# VME_buffers_address.net
KiCad netlist of a schematic drawn in Altium Designer
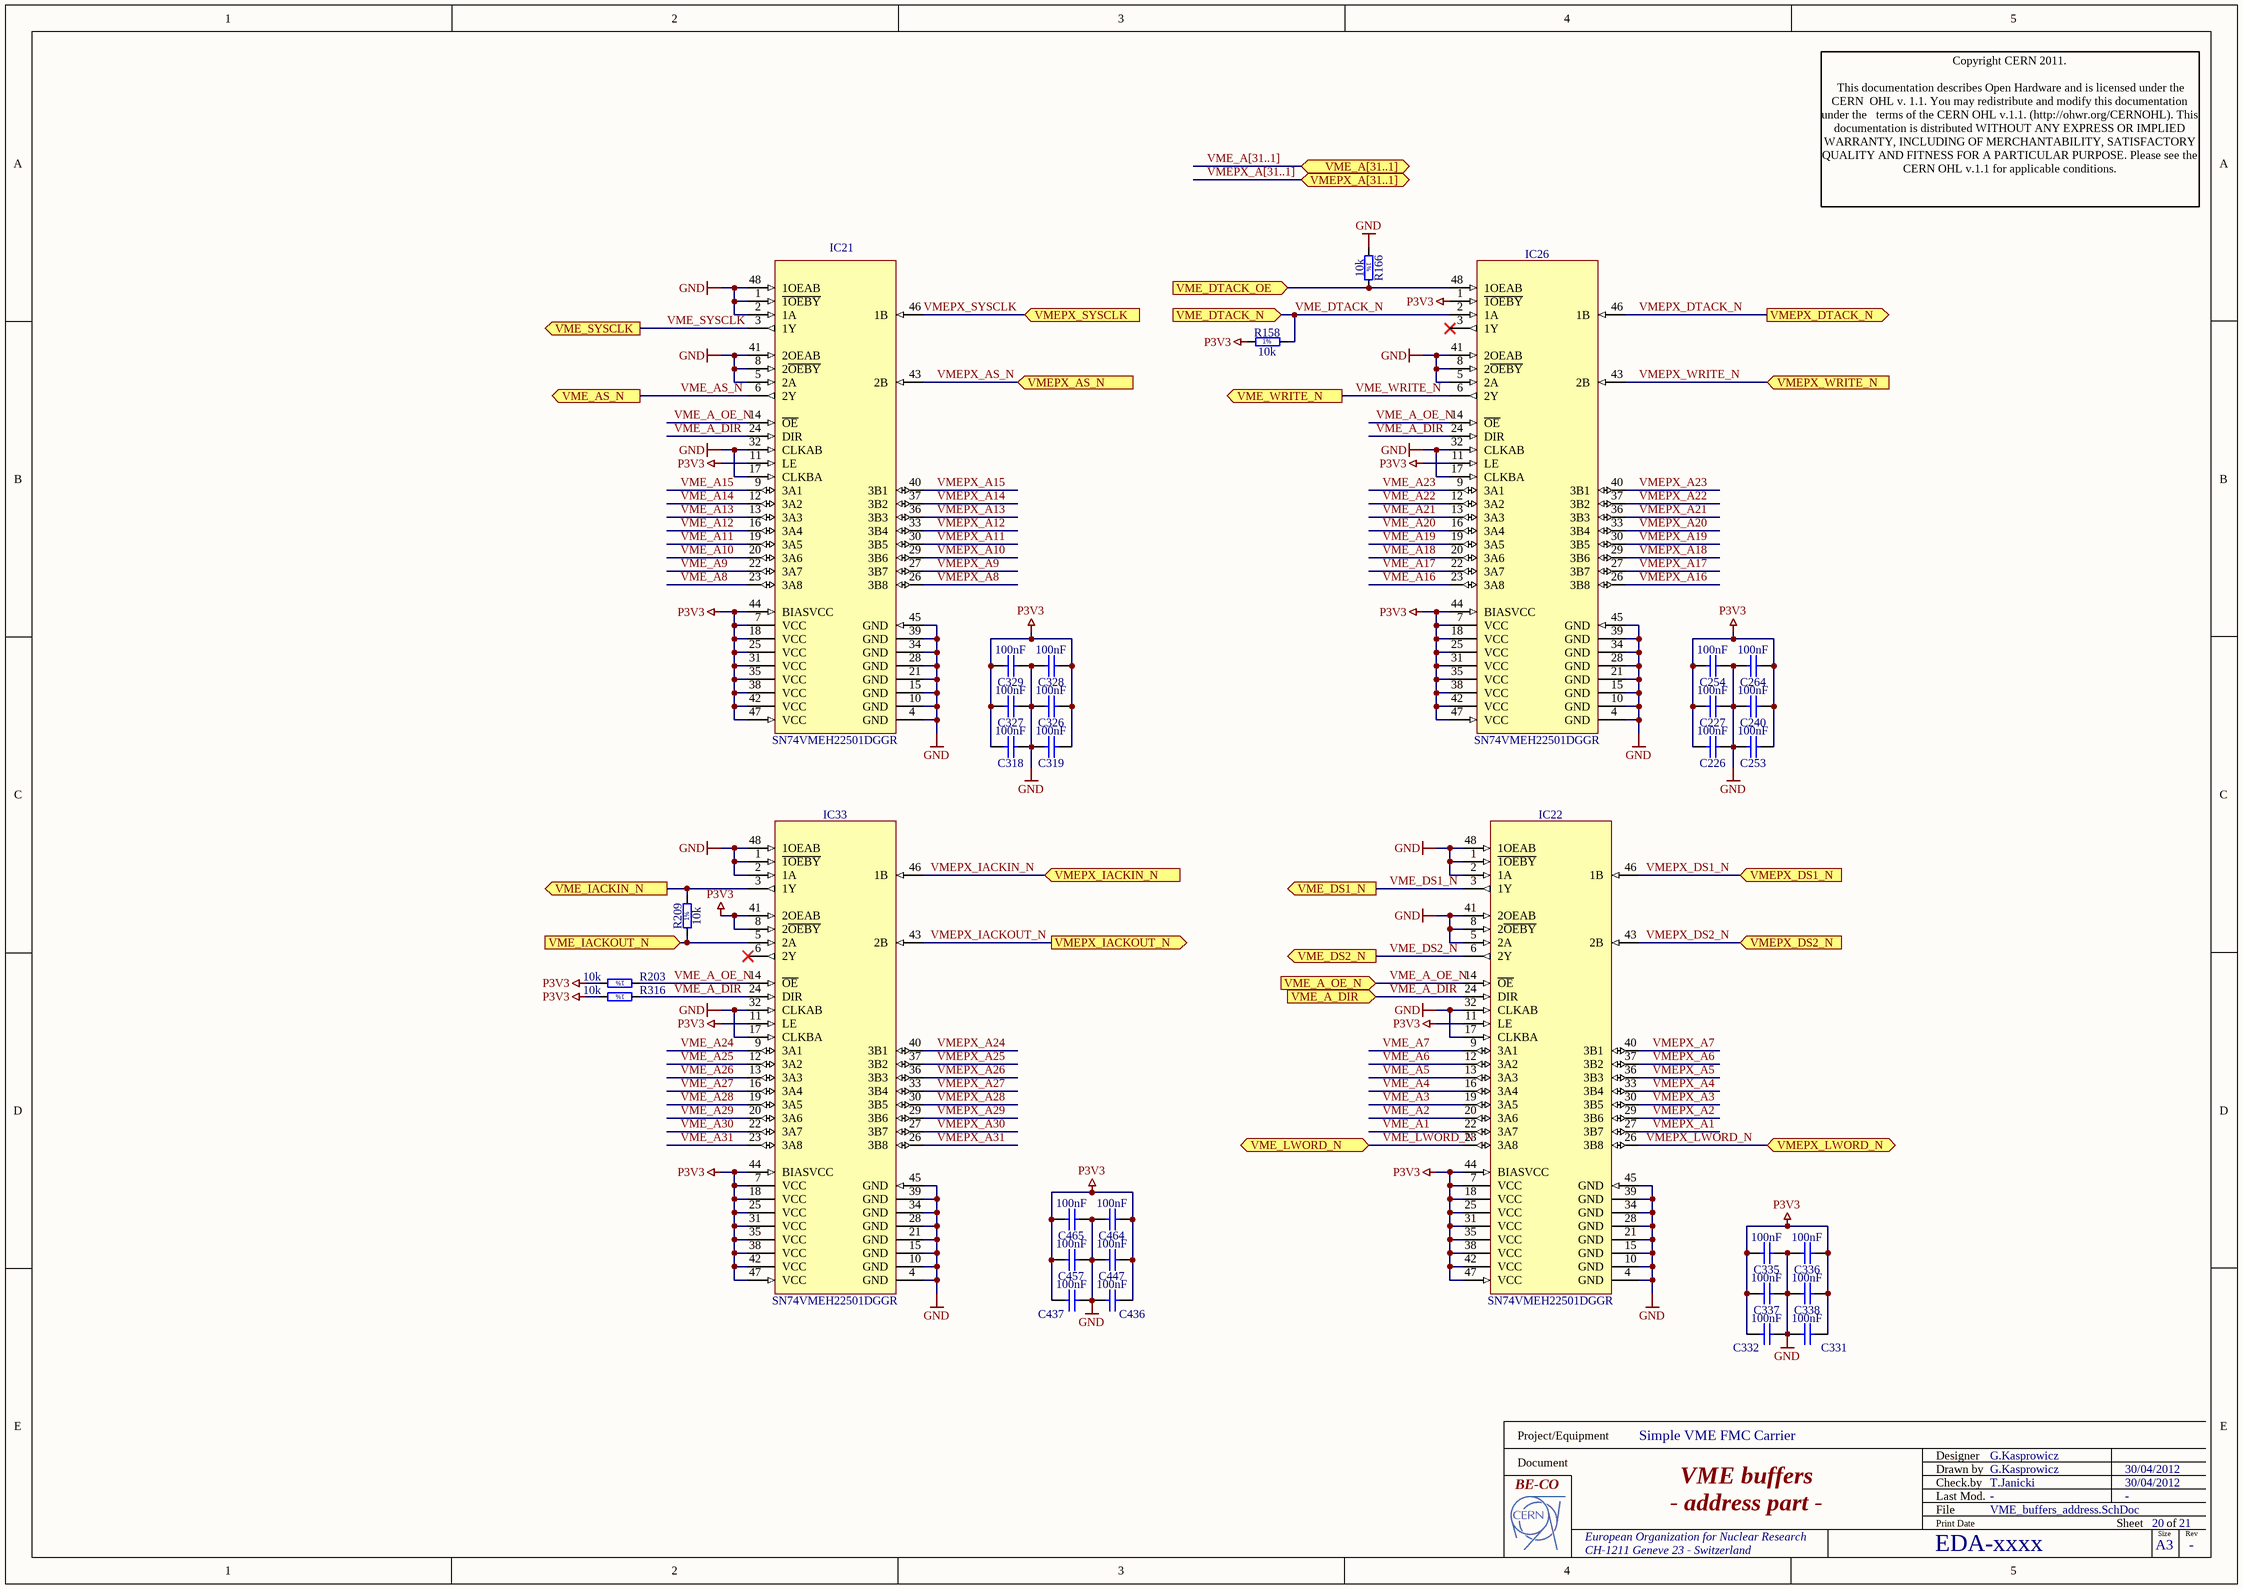
[diagram p0: VME_buffers_address.SchDoc]

(export (version "E")
  (design (tool "Eeschema 10.0.6"))
  (components
    (comp (ref "C226")
      (value "100nF")
      (footprint "CAPC1005X55N")
      (description "Non-polarised capacitor")
      (fields
        (field (name "PART NUMBER") "CC0402_100NF_16V_10%_X7R")
        (field (name "VOLTAGE") "16V")
        (field (name "AUTHOR") "CERN DEM JLC")
      )
      (libsource (lib "Capacitors") (part "Capacitor - non polarized"))
    )
    (comp (ref "C227")
      (value "100nF")
      (footprint "CAPC1005X55N")
      (description "Non-polarised capacitor")
      (fields
        (field (name "PART NUMBER") "CC0402_100NF_16V_10%_X7R")
        (field (name "VOLTAGE") "16V")
        (field (name "AUTHOR") "CERN DEM JLC")
      )
      (libsource (lib "Capacitors") (part "Capacitor - non polarized"))
    )
    (comp (ref "C240")
      (value "100nF")
      (footprint "CAPC1005X55N")
      (description "Non-polarised capacitor")
      (fields
        (field (name "PART NUMBER") "CC0402_100NF_16V_10%_X7R")
        (field (name "VOLTAGE") "16V")
        (field (name "AUTHOR") "CERN DEM JLC")
      )
      (libsource (lib "Capacitors") (part "Capacitor - non polarized"))
    )
    (comp (ref "C253")
      (value "100nF")
      (footprint "CAPC1005X55N")
      (description "Non-polarised capacitor")
      (fields
        (field (name "PART NUMBER") "CC0402_100NF_16V_10%_X7R")
        (field (name "VOLTAGE") "16V")
        (field (name "AUTHOR") "CERN DEM JLC")
      )
      (libsource (lib "Capacitors") (part "Capacitor - non polarized"))
    )
    (comp (ref "C254")
      (value "100nF")
      (footprint "CAPC1005X55N")
      (description "Non-polarised capacitor")
      (fields
        (field (name "PART NUMBER") "CC0402_100NF_16V_10%_X7R")
        (field (name "VOLTAGE") "16V")
        (field (name "AUTHOR") "CERN DEM JLC")
      )
      (libsource (lib "Capacitors") (part "Capacitor - non polarized"))
    )
    (comp (ref "C264")
      (value "100nF")
      (footprint "CAPC1005X55N")
      (description "Non-polarised capacitor")
      (fields
        (field (name "PART NUMBER") "CC0402_100NF_16V_10%_X7R")
        (field (name "VOLTAGE") "16V")
        (field (name "AUTHOR") "CERN DEM JLC")
      )
      (libsource (lib "Capacitors") (part "Capacitor - non polarized"))
    )
    (comp (ref "C318")
      (value "100nF")
      (footprint "CAPC1005X55N")
      (description "Non-polarised capacitor")
      (fields
        (field (name "PART NUMBER") "CC0402_100NF_16V_10%_X7R")
        (field (name "VOLTAGE") "16V")
        (field (name "AUTHOR") "CERN DEM JLC")
      )
      (libsource (lib "Capacitors") (part "Capacitor - non polarized"))
    )
    (comp (ref "C319")
      (value "100nF")
      (footprint "CAPC1005X55N")
      (description "Non-polarised capacitor")
      (fields
        (field (name "PART NUMBER") "CC0402_100NF_16V_10%_X7R")
        (field (name "VOLTAGE") "16V")
        (field (name "AUTHOR") "CERN DEM JLC")
      )
      (libsource (lib "Capacitors") (part "Capacitor - non polarized"))
    )
    (comp (ref "C326")
      (value "100nF")
      (footprint "CAPC1005X55N")
      (description "Non-polarised capacitor")
      (fields
        (field (name "PART NUMBER") "CC0402_100NF_16V_10%_X7R")
        (field (name "VOLTAGE") "16V")
        (field (name "AUTHOR") "CERN DEM JLC")
      )
      (libsource (lib "Capacitors") (part "Capacitor - non polarized"))
    )
    (comp (ref "C327")
      (value "100nF")
      (footprint "CAPC1005X55N")
      (description "Non-polarised capacitor")
      (fields
        (field (name "PART NUMBER") "CC0402_100NF_16V_10%_X7R")
        (field (name "VOLTAGE") "16V")
        (field (name "AUTHOR") "CERN DEM JLC")
      )
      (libsource (lib "Capacitors") (part "Capacitor - non polarized"))
    )
    (comp (ref "C328")
      (value "100nF")
      (footprint "CAPC1005X55N")
      (description "Non-polarised capacitor")
      (fields
        (field (name "PART NUMBER") "CC0402_100NF_16V_10%_X7R")
        (field (name "VOLTAGE") "16V")
        (field (name "AUTHOR") "CERN DEM JLC")
      )
      (libsource (lib "Capacitors") (part "Capacitor - non polarized"))
    )
    (comp (ref "C329")
      (value "100nF")
      (footprint "CAPC1005X55N")
      (description "Non-polarised capacitor")
      (fields
        (field (name "PART NUMBER") "CC0402_100NF_16V_10%_X7R")
        (field (name "VOLTAGE") "16V")
        (field (name "AUTHOR") "CERN DEM JLC")
      )
      (libsource (lib "Capacitors") (part "Capacitor - non polarized"))
    )
    (comp (ref "C331")
      (value "100nF")
      (footprint "CAPC1005X55N")
      (description "Non-polarised capacitor")
      (fields
        (field (name "PART NUMBER") "CC0402_100NF_16V_10%_X7R")
        (field (name "VOLTAGE") "16V")
        (field (name "AUTHOR") "CERN DEM JLC")
      )
      (libsource (lib "Capacitors") (part "Capacitor - non polarized"))
    )
    (comp (ref "C332")
      (value "100nF")
      (footprint "CAPC1005X55N")
      (description "Non-polarised capacitor")
      (fields
        (field (name "PART NUMBER") "CC0402_100NF_16V_10%_X7R")
        (field (name "VOLTAGE") "16V")
        (field (name "AUTHOR") "CERN DEM JLC")
      )
      (libsource (lib "Capacitors") (part "Capacitor - non polarized"))
    )
    (comp (ref "C335")
      (value "100nF")
      (footprint "CAPC1005X55N")
      (description "Non-polarised capacitor")
      (fields
        (field (name "PART NUMBER") "CC0402_100NF_16V_10%_X7R")
        (field (name "VOLTAGE") "16V")
        (field (name "AUTHOR") "CERN DEM JLC")
      )
      (libsource (lib "Capacitors") (part "Capacitor - non polarized"))
    )
    (comp (ref "C336")
      (value "100nF")
      (footprint "CAPC1005X55N")
      (description "Non-polarised capacitor")
      (fields
        (field (name "PART NUMBER") "CC0402_100NF_16V_10%_X7R")
        (field (name "VOLTAGE") "16V")
        (field (name "AUTHOR") "CERN DEM JLC")
      )
      (libsource (lib "Capacitors") (part "Capacitor - non polarized"))
    )
    (comp (ref "C337")
      (value "100nF")
      (footprint "CAPC1005X55N")
      (description "Non-polarised capacitor")
      (fields
        (field (name "PART NUMBER") "CC0402_100NF_16V_10%_X7R")
        (field (name "VOLTAGE") "16V")
        (field (name "AUTHOR") "CERN DEM JLC")
      )
      (libsource (lib "Capacitors") (part "Capacitor - non polarized"))
    )
    (comp (ref "C338")
      (value "100nF")
      (footprint "CAPC1005X55N")
      (description "Non-polarised capacitor")
      (fields
        (field (name "PART NUMBER") "CC0402_100NF_16V_10%_X7R")
        (field (name "VOLTAGE") "16V")
        (field (name "AUTHOR") "CERN DEM JLC")
      )
      (libsource (lib "Capacitors") (part "Capacitor - non polarized"))
    )
    (comp (ref "C436")
      (value "100nF")
      (footprint "CAPC1005X55N")
      (description "Non-polarised capacitor")
      (fields
        (field (name "PART NUMBER") "CC0402_100NF_16V_10%_X7R")
        (field (name "VOLTAGE") "16V")
        (field (name "AUTHOR") "CERN DEM JLC")
      )
      (libsource (lib "Capacitors") (part "Capacitor - non polarized"))
    )
    (comp (ref "C437")
      (value "100nF")
      (footprint "CAPC1005X55N")
      (description "Non-polarised capacitor")
      (fields
        (field (name "PART NUMBER") "CC0402_100NF_16V_10%_X7R")
        (field (name "VOLTAGE") "16V")
        (field (name "AUTHOR") "CERN DEM JLC")
      )
      (libsource (lib "Capacitors") (part "Capacitor - non polarized"))
    )
    (comp (ref "C447")
      (value "100nF")
      (footprint "CAPC1005X55N")
      (description "Non-polarised capacitor")
      (fields
        (field (name "PART NUMBER") "CC0402_100NF_16V_10%_X7R")
        (field (name "VOLTAGE") "16V")
        (field (name "AUTHOR") "CERN DEM JLC")
      )
      (libsource (lib "Capacitors") (part "Capacitor - non polarized"))
    )
    (comp (ref "C457")
      (value "100nF")
      (footprint "CAPC1005X55N")
      (description "Non-polarised capacitor")
      (fields
        (field (name "PART NUMBER") "CC0402_100NF_16V_10%_X7R")
        (field (name "VOLTAGE") "16V")
        (field (name "AUTHOR") "CERN DEM JLC")
      )
      (libsource (lib "Capacitors") (part "Capacitor - non polarized"))
    )
    (comp (ref "C464")
      (value "100nF")
      (footprint "CAPC1005X55N")
      (description "Non-polarised capacitor")
      (fields
        (field (name "PART NUMBER") "CC0402_100NF_16V_10%_X7R")
        (field (name "VOLTAGE") "16V")
        (field (name "AUTHOR") "CERN DEM JLC")
      )
      (libsource (lib "Capacitors") (part "Capacitor - non polarized"))
    )
    (comp (ref "C465")
      (value "100nF")
      (footprint "CAPC1005X55N")
      (description "Non-polarised capacitor")
      (fields
        (field (name "PART NUMBER") "CC0402_100NF_16V_10%_X7R")
        (field (name "VOLTAGE") "16V")
        (field (name "AUTHOR") "CERN DEM JLC")
      )
      (libsource (lib "Capacitors") (part "Capacitor - non polarized"))
    )
    (comp (ref "IC21")
      (value "SN74VMEH22501DGGR")
      (footprint "SOP50P810X120-48N")
      (description "8-Bit Universal Bus Transceiver and Two 1-Bit Bus Transceivers with 3-State Outputs")
      (fields (field (name "MANUFACTURER") "TEXAS INSTRUMENTS") (field (name "AUTHOR") "CERN DEM JLC"))
      (libsource (lib "ICs And Semiconductors") (part "74VMEH22501"))
    )
    (comp (ref "IC22")
      (value "SN74VMEH22501DGGR")
      (footprint "SOP50P810X120-48N")
      (description "8-Bit Universal Bus Transceiver and Two 1-Bit Bus Transceivers with 3-State Outputs")
      (fields (field (name "MANUFACTURER") "TEXAS INSTRUMENTS") (field (name "AUTHOR") "CERN DEM JLC"))
      (libsource (lib "ICs And Semiconductors") (part "74VMEH22501"))
    )
    (comp (ref "IC26")
      (value "SN74VMEH22501DGGR")
      (footprint "SOP50P810X120-48N")
      (description "8-Bit Universal Bus Transceiver and Two 1-Bit Bus Transceivers with 3-State Outputs")
      (fields (field (name "MANUFACTURER") "TEXAS INSTRUMENTS") (field (name "AUTHOR") "CERN DEM JLC"))
      (libsource (lib "ICs And Semiconductors") (part "74VMEH22501"))
    )
    (comp (ref "IC33")
      (value "SN74VMEH22501DGGR")
      (footprint "SOP50P810X120-48N")
      (description "8-Bit Universal Bus Transceiver and Two 1-Bit Bus Transceivers with 3-State Outputs")
      (fields (field (name "MANUFACTURER") "TEXAS INSTRUMENTS") (field (name "AUTHOR") "CERN DEM JLC"))
      (libsource (lib "ICs And Semiconductors") (part "74VMEH22501"))
    )
    (comp (ref "R158")
      (value "10k")
      (footprint "RESC1608X55N")
      (description "Resistor - 1%")
      (fields
        (field (name "PART NUMBER") "R0603_10K_1%_0.1W_100PPM")
        (field (name "POWER") "0.1W")
        (field (name "AUTHOR") "CERN DEM JLC")
      )
      (libsource (lib "Resistors") (part "Resistor - 1%"))
    )
    (comp (ref "R166")
      (value "10k")
      (footprint "RESC1608X55N")
      (description "Resistor - 1%")
      (fields
        (field (name "PART NUMBER") "R0603_10K_1%_0.1W_100PPM")
        (field (name "POWER") "0.1W")
        (field (name "AUTHOR") "CERN DEM JLC")
      )
      (libsource (lib "Resistors") (part "Resistor - 1%"))
    )
    (comp (ref "R203")
      (value "10k")
      (footprint "RESC1608X55N")
      (description "Resistor - 1%")
      (fields
        (field (name "PART NUMBER") "R0603_10K_1%_0.1W_100PPM")
        (field (name "POWER") "0.1W")
        (field (name "AUTHOR") "CERN DEM JLC")
      )
      (libsource (lib "Resistors") (part "Resistor - 1%"))
    )
    (comp (ref "R209")
      (value "10k")
      (footprint "RESC1608X55N")
      (description "Resistor - 1%")
      (fields
        (field (name "PART NUMBER") "R0603_10K_1%_0.1W_100PPM")
        (field (name "POWER") "0.1W")
        (field (name "AUTHOR") "CERN DEM JLC")
      )
      (libsource (lib "Resistors") (part "Resistor - 1%"))
    )
    (comp (ref "R316")
      (value "10k")
      (footprint "RESC1608X55N")
      (description "Resistor - 1%")
      (fields
        (field (name "PART NUMBER") "R0603_10K_1%_0.1W_100PPM")
        (field (name "POWER") "0.1W")
        (field (name "AUTHOR") "CERN DEM JLC")
      )
      (libsource (lib "Resistors") (part "Resistor - 1%"))
    )
  )
  (nets
    (net (code "1") (name "/VMEPX_A1") (class "Default")
      (node (ref "IC22") (pin "27") (pinfunction "3B7_27") (pintype "bidirectional"))
    )
    (net (code "2") (name "/VMEPX_A2") (class "Default")
      (node (ref "IC22") (pin "29") (pinfunction "3B6_29") (pintype "bidirectional"))
    )
    (net (code "3") (name "/VMEPX_A3") (class "Default")
      (node (ref "IC22") (pin "30") (pinfunction "3B5_30") (pintype "bidirectional"))
    )
    (net (code "4") (name "/VMEPX_A4") (class "Default")
      (node (ref "IC22") (pin "33") (pinfunction "3B4_33") (pintype "bidirectional"))
    )
    (net (code "5") (name "/VMEPX_A5") (class "Default")
      (node (ref "IC22") (pin "36") (pinfunction "3B3_36") (pintype "bidirectional"))
    )
    (net (code "6") (name "/VMEPX_A6") (class "Default")
      (node (ref "IC22") (pin "37") (pinfunction "3B2_37") (pintype "bidirectional"))
    )
    (net (code "7") (name "/VMEPX_A7") (class "Default")
      (node (ref "IC22") (pin "40") (pinfunction "3B1_40") (pintype "bidirectional"))
    )
    (net (code "8") (name "/VMEPX_A8") (class "Default")
      (node (ref "IC21") (pin "26") (pinfunction "3B8_26") (pintype "bidirectional"))
    )
    (net (code "9") (name "/VMEPX_A9") (class "Default")
      (node (ref "IC21") (pin "27") (pinfunction "3B7_27") (pintype "bidirectional"))
    )
    (net (code "10") (name "/VMEPX_A10") (class "Default")
      (node (ref "IC21") (pin "29") (pinfunction "3B6_29") (pintype "bidirectional"))
    )
    (net (code "11") (name "/VMEPX_A11") (class "Default")
      (node (ref "IC21") (pin "30") (pinfunction "3B5_30") (pintype "bidirectional"))
    )
    (net (code "12") (name "/VMEPX_A12") (class "Default")
      (node (ref "IC21") (pin "33") (pinfunction "3B4_33") (pintype "bidirectional"))
    )
    (net (code "13") (name "/VMEPX_A13") (class "Default")
      (node (ref "IC21") (pin "36") (pinfunction "3B3_36") (pintype "bidirectional"))
    )
    (net (code "14") (name "/VMEPX_A14") (class "Default")
      (node (ref "IC21") (pin "37") (pinfunction "3B2_37") (pintype "bidirectional"))
    )
    (net (code "15") (name "/VMEPX_A15") (class "Default")
      (node (ref "IC21") (pin "40") (pinfunction "3B1_40") (pintype "bidirectional"))
    )
    (net (code "16") (name "/VMEPX_A16") (class "Default")
      (node (ref "IC26") (pin "26") (pinfunction "3B8_26") (pintype "bidirectional"))
    )
    (net (code "17") (name "/VMEPX_A17") (class "Default")
      (node (ref "IC26") (pin "27") (pinfunction "3B7_27") (pintype "bidirectional"))
    )
    (net (code "18") (name "/VMEPX_A18") (class "Default")
      (node (ref "IC26") (pin "29") (pinfunction "3B6_29") (pintype "bidirectional"))
    )
    (net (code "19") (name "/VMEPX_A19") (class "Default")
      (node (ref "IC26") (pin "30") (pinfunction "3B5_30") (pintype "bidirectional"))
    )
    (net (code "20") (name "/VMEPX_A20") (class "Default")
      (node (ref "IC26") (pin "33") (pinfunction "3B4_33") (pintype "bidirectional"))
    )
    (net (code "21") (name "/VMEPX_A21") (class "Default")
      (node (ref "IC26") (pin "36") (pinfunction "3B3_36") (pintype "bidirectional"))
    )
    (net (code "22") (name "/VMEPX_A22") (class "Default")
      (node (ref "IC26") (pin "37") (pinfunction "3B2_37") (pintype "bidirectional"))
    )
    (net (code "23") (name "/VMEPX_A23") (class "Default")
      (node (ref "IC26") (pin "40") (pinfunction "3B1_40") (pintype "bidirectional"))
    )
    (net (code "24") (name "/VMEPX_A24") (class "Default")
      (node (ref "IC33") (pin "40") (pinfunction "3B1_40") (pintype "bidirectional"))
    )
    (net (code "25") (name "/VMEPX_A25") (class "Default")
      (node (ref "IC33") (pin "37") (pinfunction "3B2_37") (pintype "bidirectional"))
    )
    (net (code "26") (name "/VMEPX_A26") (class "Default")
      (node (ref "IC33") (pin "36") (pinfunction "3B3_36") (pintype "bidirectional"))
    )
    (net (code "27") (name "/VMEPX_A27") (class "Default")
      (node (ref "IC33") (pin "33") (pinfunction "3B4_33") (pintype "bidirectional"))
    )
    (net (code "28") (name "/VMEPX_A28") (class "Default")
      (node (ref "IC33") (pin "30") (pinfunction "3B5_30") (pintype "bidirectional"))
    )
    (net (code "29") (name "/VMEPX_A29") (class "Default")
      (node (ref "IC33") (pin "29") (pinfunction "3B6_29") (pintype "bidirectional"))
    )
    (net (code "30") (name "/VMEPX_A30") (class "Default")
      (node (ref "IC33") (pin "27") (pinfunction "3B7_27") (pintype "bidirectional"))
    )
    (net (code "31") (name "/VMEPX_A31") (class "Default")
      (node (ref "IC33") (pin "26") (pinfunction "3B8_26") (pintype "bidirectional"))
    )
    (net (code "32") (name "/VMEPX_AS_N") (class "Default")
      (node (ref "IC21") (pin "43") (pinfunction "2B_43") (pintype "input"))
    )
    (net (code "34") (name "/VMEPX_DS1_N") (class "Default")
      (node (ref "IC22") (pin "46") (pinfunction "1B_46") (pintype "input"))
    )
    (net (code "35") (name "/VMEPX_DS2_N") (class "Default")
      (node (ref "IC22") (pin "43") (pinfunction "2B_43") (pintype "input"))
    )
    (net (code "36") (name "/VMEPX_DTACK_N") (class "Default")
      (node (ref "IC26") (pin "46") (pinfunction "1B_46") (pintype "input"))
    )
    (net (code "37") (name "/VMEPX_IACKIN_N") (class "Default")
      (node (ref "IC33") (pin "46") (pinfunction "1B_46") (pintype "input"))
    )
    (net (code "38") (name "/VMEPX_IACKOUT_N") (class "Default")
      (node (ref "IC33") (pin "43") (pinfunction "2B_43") (pintype "input"))
    )
    (net (code "39") (name "/VMEPX_LWORD_N") (class "Default")
      (node (ref "IC22") (pin "26") (pinfunction "3B8_26") (pintype "bidirectional"))
    )
    (net (code "40") (name "/VMEPX_SYSCLK") (class "Default")
      (node (ref "IC21") (pin "46") (pinfunction "1B_46") (pintype "input"))
    )
    (net (code "41") (name "/VMEPX_WRITE_N") (class "Default")
      (node (ref "IC26") (pin "43") (pinfunction "2B_43") (pintype "input"))
    )
    (net (code "42") (name "/VME_A1") (class "Default")
      (node (ref "IC22") (pin "22") (pinfunction "3A7_22") (pintype "bidirectional"))
    )
    (net (code "43") (name "/VME_A2") (class "Default")
      (node (ref "IC22") (pin "20") (pinfunction "3A6_20") (pintype "bidirectional"))
    )
    (net (code "44") (name "/VME_A3") (class "Default")
      (node (ref "IC22") (pin "19") (pinfunction "3A5_19") (pintype "bidirectional"))
    )
    (net (code "45") (name "/VME_A4") (class "Default")
      (node (ref "IC22") (pin "16") (pinfunction "3A4_16") (pintype "bidirectional"))
    )
    (net (code "46") (name "/VME_A5") (class "Default")
      (node (ref "IC22") (pin "13") (pinfunction "3A3_13") (pintype "bidirectional"))
    )
    (net (code "47") (name "/VME_A6") (class "Default")
      (node (ref "IC22") (pin "12") (pinfunction "3A2_12") (pintype "bidirectional"))
    )
    (net (code "48") (name "/VME_A7") (class "Default")
      (node (ref "IC22") (pin "9") (pinfunction "3A1_9") (pintype "bidirectional"))
    )
    (net (code "49") (name "/VME_A8") (class "Default")
      (node (ref "IC21") (pin "23") (pinfunction "3A8_23") (pintype "bidirectional"))
    )
    (net (code "50") (name "/VME_A9") (class "Default")
      (node (ref "IC21") (pin "22") (pinfunction "3A7_22") (pintype "bidirectional"))
    )
    (net (code "51") (name "/VME_A10") (class "Default")
      (node (ref "IC21") (pin "20") (pinfunction "3A6_20") (pintype "bidirectional"))
    )
    (net (code "52") (name "/VME_A11") (class "Default")
      (node (ref "IC21") (pin "19") (pinfunction "3A5_19") (pintype "bidirectional"))
    )
    (net (code "53") (name "/VME_A12") (class "Default")
      (node (ref "IC21") (pin "16") (pinfunction "3A4_16") (pintype "bidirectional"))
    )
    (net (code "54") (name "/VME_A13") (class "Default")
      (node (ref "IC21") (pin "13") (pinfunction "3A3_13") (pintype "bidirectional"))
    )
    (net (code "55") (name "/VME_A14") (class "Default")
      (node (ref "IC21") (pin "12") (pinfunction "3A2_12") (pintype "bidirectional"))
    )
    (net (code "56") (name "/VME_A15") (class "Default")
      (node (ref "IC21") (pin "9") (pinfunction "3A1_9") (pintype "bidirectional"))
    )
    (net (code "57") (name "/VME_A16") (class "Default")
      (node (ref "IC26") (pin "23") (pinfunction "3A8_23") (pintype "bidirectional"))
    )
    (net (code "58") (name "/VME_A17") (class "Default")
      (node (ref "IC26") (pin "22") (pinfunction "3A7_22") (pintype "bidirectional"))
    )
    (net (code "59") (name "/VME_A18") (class "Default")
      (node (ref "IC26") (pin "20") (pinfunction "3A6_20") (pintype "bidirectional"))
    )
    (net (code "60") (name "/VME_A19") (class "Default")
      (node (ref "IC26") (pin "19") (pinfunction "3A5_19") (pintype "bidirectional"))
    )
    (net (code "61") (name "/VME_A20") (class "Default")
      (node (ref "IC26") (pin "16") (pinfunction "3A4_16") (pintype "bidirectional"))
    )
    (net (code "62") (name "/VME_A21") (class "Default")
      (node (ref "IC26") (pin "13") (pinfunction "3A3_13") (pintype "bidirectional"))
    )
    (net (code "63") (name "/VME_A22") (class "Default")
      (node (ref "IC26") (pin "12") (pinfunction "3A2_12") (pintype "bidirectional"))
    )
    (net (code "64") (name "/VME_A23") (class "Default")
      (node (ref "IC26") (pin "9") (pinfunction "3A1_9") (pintype "bidirectional"))
    )
    (net (code "65") (name "/VME_A24") (class "Default")
      (node (ref "IC33") (pin "9") (pinfunction "3A1_9") (pintype "bidirectional"))
    )
    (net (code "66") (name "/VME_A25") (class "Default")
      (node (ref "IC33") (pin "12") (pinfunction "3A2_12") (pintype "bidirectional"))
    )
    (net (code "67") (name "/VME_A26") (class "Default")
      (node (ref "IC33") (pin "13") (pinfunction "3A3_13") (pintype "bidirectional"))
    )
    (net (code "68") (name "/VME_A27") (class "Default")
      (node (ref "IC33") (pin "16") (pinfunction "3A4_16") (pintype "bidirectional"))
    )
    (net (code "69") (name "/VME_A28") (class "Default")
      (node (ref "IC33") (pin "19") (pinfunction "3A5_19") (pintype "bidirectional"))
    )
    (net (code "70") (name "/VME_A29") (class "Default")
      (node (ref "IC33") (pin "20") (pinfunction "3A6_20") (pintype "bidirectional"))
    )
    (net (code "71") (name "/VME_A30") (class "Default")
      (node (ref "IC33") (pin "22") (pinfunction "3A7_22") (pintype "bidirectional"))
    )
    (net (code "72") (name "/VME_A31") (class "Default")
      (node (ref "IC33") (pin "23") (pinfunction "3A8_23") (pintype "bidirectional"))
    )
    (net (code "73") (name "/VME_AS_N") (class "Default")
      (node (ref "IC21") (pin "6") (pinfunction "2Y_6") (pintype "output"))
    )
    (net (code "75") (name "/VME_A_DIR") (class "Default")
      (node (ref "IC21") (pin "24") (pinfunction "DIR_24") (pintype "input"))
      (node (ref "IC22") (pin "24") (pinfunction "DIR_24") (pintype "input"))
      (node (ref "IC26") (pin "24") (pinfunction "DIR_24") (pintype "input"))
      (node (ref "IC33") (pin "24") (pinfunction "DIR_24") (pintype "input"))
      (node (ref "R316") (pin "1") (pinfunction "1_1") (pintype "passive"))
    )
    (net (code "76") (name "/VME_A_OE_N") (class "Default")
      (node (ref "IC21") (pin "14") (pinfunction "~{OE}_14") (pintype "input"))
      (node (ref "IC22") (pin "14") (pinfunction "~{OE}_14") (pintype "input"))
      (node (ref "IC26") (pin "14") (pinfunction "~{OE}_14") (pintype "input"))
      (node (ref "IC33") (pin "14") (pinfunction "~{OE}_14") (pintype "input"))
      (node (ref "R203") (pin "1") (pinfunction "1_1") (pintype "passive"))
    )
    (net (code "77") (name "/VME_DS1_N") (class "Default")
      (node (ref "IC22") (pin "3") (pinfunction "1Y_3") (pintype "output"))
    )
    (net (code "78") (name "/VME_DS2_N") (class "Default")
      (node (ref "IC22") (pin "6") (pinfunction "2Y_6") (pintype "output"))
    )
    (net (code "79") (name "/VME_DTACK_N") (class "Default")
      (node (ref "IC26") (pin "2") (pinfunction "1A_2") (pintype "input"))
      (node (ref "R158") (pin "2") (pinfunction "2_2") (pintype "passive"))
    )
    (net (code "80") (name "/VME_DTACK_OE") (class "Default")
      (node (ref "IC26") (pin "48") (pinfunction "1OEAB_48") (pintype "input"))
      (node (ref "R166") (pin "2") (pinfunction "2_2") (pintype "passive"))
    )
    (net (code "81") (name "/VME_IACKIN_N") (class "Default")
      (node (ref "IC33") (pin "3") (pinfunction "1Y_3") (pintype "output"))
      (node (ref "R209") (pin "2") (pinfunction "2_2") (pintype "passive"))
    )
    (net (code "82") (name "/VME_IACKOUT_N") (class "Default")
      (node (ref "IC33") (pin "5") (pinfunction "2A_5") (pintype "input"))
      (node (ref "R209") (pin "1") (pinfunction "1_1") (pintype "passive"))
    )
    (net (code "83") (name "/VME_LWORD_N") (class "Default")
      (node (ref "IC22") (pin "23") (pinfunction "3A8_23") (pintype "bidirectional"))
    )
    (net (code "84") (name "/VME_SYSCLK") (class "Default")
      (node (ref "IC21") (pin "3") (pinfunction "1Y_3") (pintype "output"))
    )
    (net (code "85") (name "/VME_WRITE_N") (class "Default")
      (node (ref "IC26") (pin "6") (pinfunction "2Y_6") (pintype "output"))
    )
    (net (code "86") (name "GND") (class "Default")
      (node (ref "C226") (pin "1") (pinfunction "1_1") (pintype "passive"))
      (node (ref "C227") (pin "1") (pinfunction "1_1") (pintype "passive"))
      (node (ref "C240") (pin "2") (pinfunction "2_2") (pintype "passive"))
      (node (ref "C253") (pin "2") (pinfunction "2_2") (pintype "passive"))
      (node (ref "C254") (pin "1") (pinfunction "1_1") (pintype "passive"))
      (node (ref "C264") (pin "2") (pinfunction "2_2") (pintype "passive"))
      (node (ref "C318") (pin "1") (pinfunction "1_1") (pintype "passive"))
      (node (ref "C319") (pin "2") (pinfunction "2_2") (pintype "passive"))
      (node (ref "C326") (pin "2") (pinfunction "2_2") (pintype "passive"))
      (node (ref "C327") (pin "1") (pinfunction "1_1") (pintype "passive"))
      (node (ref "C328") (pin "2") (pinfunction "2_2") (pintype "passive"))
      (node (ref "C329") (pin "1") (pinfunction "1_1") (pintype "passive"))
      (node (ref "C331") (pin "2") (pinfunction "2_2") (pintype "passive"))
      (node (ref "C332") (pin "1") (pinfunction "1_1") (pintype "passive"))
      (node (ref "C335") (pin "1") (pinfunction "1_1") (pintype "passive"))
      (node (ref "C336") (pin "2") (pinfunction "2_2") (pintype "passive"))
      (node (ref "C337") (pin "1") (pinfunction "1_1") (pintype "passive"))
      (node (ref "C338") (pin "2") (pinfunction "2_2") (pintype "passive"))
      (node (ref "C436") (pin "2") (pinfunction "2_2") (pintype "passive"))
      (node (ref "C437") (pin "1") (pinfunction "1_1") (pintype "passive"))
      (node (ref "C447") (pin "2") (pinfunction "2_2") (pintype "passive"))
      (node (ref "C457") (pin "1") (pinfunction "1_1") (pintype "passive"))
      (node (ref "C464") (pin "2") (pinfunction "2_2") (pintype "passive"))
      (node (ref "C465") (pin "1") (pinfunction "1_1") (pintype "passive"))
      (node (ref "IC21") (pin "1") (pinfunction "~{1OEBY}_1") (pintype "input"))
      (node (ref "IC21") (pin "10") (pinfunction "GND_10") (pintype "power_in"))
      (node (ref "IC21") (pin "15") (pinfunction "GND_15") (pintype "power_in"))
      (node (ref "IC21") (pin "17") (pinfunction "CLKBA_17") (pintype "input"))
      (node (ref "IC21") (pin "2") (pinfunction "1A_2") (pintype "input"))
      (node (ref "IC21") (pin "21") (pinfunction "GND_21") (pintype "power_in"))
      (node (ref "IC21") (pin "28") (pinfunction "GND_28") (pintype "power_in"))
      (node (ref "IC21") (pin "32") (pinfunction "CLKAB_32") (pintype "input"))
      (node (ref "IC21") (pin "34") (pinfunction "GND_34") (pintype "power_in"))
      (node (ref "IC21") (pin "39") (pinfunction "GND_39") (pintype "power_in"))
      (node (ref "IC21") (pin "4") (pinfunction "GND_4") (pintype "power_in"))
      (node (ref "IC21") (pin "41") (pinfunction "2OEAB_41") (pintype "input"))
      (node (ref "IC21") (pin "45") (pinfunction "GND_45") (pintype "input"))
      (node (ref "IC21") (pin "48") (pinfunction "1OEAB_48") (pintype "input"))
      (node (ref "IC21") (pin "5") (pinfunction "2A_5") (pintype "input"))
      (node (ref "IC21") (pin "8") (pinfunction "2~{OEBY}_8") (pintype "input"))
      (node (ref "IC22") (pin "1") (pinfunction "~{1OEBY}_1") (pintype "input"))
      (node (ref "IC22") (pin "10") (pinfunction "GND_10") (pintype "power_in"))
      (node (ref "IC22") (pin "15") (pinfunction "GND_15") (pintype "power_in"))
      (node (ref "IC22") (pin "17") (pinfunction "CLKBA_17") (pintype "input"))
      (node (ref "IC22") (pin "2") (pinfunction "1A_2") (pintype "input"))
      (node (ref "IC22") (pin "21") (pinfunction "GND_21") (pintype "power_in"))
      (node (ref "IC22") (pin "28") (pinfunction "GND_28") (pintype "power_in"))
      (node (ref "IC22") (pin "32") (pinfunction "CLKAB_32") (pintype "input"))
      (node (ref "IC22") (pin "34") (pinfunction "GND_34") (pintype "power_in"))
      (node (ref "IC22") (pin "39") (pinfunction "GND_39") (pintype "power_in"))
      (node (ref "IC22") (pin "4") (pinfunction "GND_4") (pintype "power_in"))
      (node (ref "IC22") (pin "41") (pinfunction "2OEAB_41") (pintype "input"))
      (node (ref "IC22") (pin "45") (pinfunction "GND_45") (pintype "input"))
      (node (ref "IC22") (pin "48") (pinfunction "1OEAB_48") (pintype "input"))
      (node (ref "IC22") (pin "5") (pinfunction "2A_5") (pintype "input"))
      (node (ref "IC22") (pin "8") (pinfunction "2~{OEBY}_8") (pintype "input"))
      (node (ref "IC26") (pin "10") (pinfunction "GND_10") (pintype "power_in"))
      (node (ref "IC26") (pin "15") (pinfunction "GND_15") (pintype "power_in"))
      (node (ref "IC26") (pin "17") (pinfunction "CLKBA_17") (pintype "input"))
      (node (ref "IC26") (pin "21") (pinfunction "GND_21") (pintype "power_in"))
      (node (ref "IC26") (pin "28") (pinfunction "GND_28") (pintype "power_in"))
      (node (ref "IC26") (pin "32") (pinfunction "CLKAB_32") (pintype "input"))
      (node (ref "IC26") (pin "34") (pinfunction "GND_34") (pintype "power_in"))
      (node (ref "IC26") (pin "39") (pinfunction "GND_39") (pintype "power_in"))
      (node (ref "IC26") (pin "4") (pinfunction "GND_4") (pintype "power_in"))
      (node (ref "IC26") (pin "41") (pinfunction "2OEAB_41") (pintype "input"))
      (node (ref "IC26") (pin "45") (pinfunction "GND_45") (pintype "input"))
      (node (ref "IC26") (pin "5") (pinfunction "2A_5") (pintype "input"))
      (node (ref "IC26") (pin "8") (pinfunction "2~{OEBY}_8") (pintype "input"))
      (node (ref "IC33") (pin "1") (pinfunction "~{1OEBY}_1") (pintype "input"))
      (node (ref "IC33") (pin "10") (pinfunction "GND_10") (pintype "power_in"))
      (node (ref "IC33") (pin "15") (pinfunction "GND_15") (pintype "power_in"))
      (node (ref "IC33") (pin "17") (pinfunction "CLKBA_17") (pintype "input"))
      (node (ref "IC33") (pin "2") (pinfunction "1A_2") (pintype "input"))
      (node (ref "IC33") (pin "21") (pinfunction "GND_21") (pintype "power_in"))
      (node (ref "IC33") (pin "28") (pinfunction "GND_28") (pintype "power_in"))
      (node (ref "IC33") (pin "32") (pinfunction "CLKAB_32") (pintype "input"))
      (node (ref "IC33") (pin "34") (pinfunction "GND_34") (pintype "power_in"))
      (node (ref "IC33") (pin "39") (pinfunction "GND_39") (pintype "power_in"))
      (node (ref "IC33") (pin "4") (pinfunction "GND_4") (pintype "power_in"))
      (node (ref "IC33") (pin "45") (pinfunction "GND_45") (pintype "input"))
      (node (ref "IC33") (pin "48") (pinfunction "1OEAB_48") (pintype "input"))
      (node (ref "R166") (pin "1") (pinfunction "1_1") (pintype "passive"))
    )
    (net (code "87") (name "P3V3") (class "Default")
      (node (ref "C226") (pin "2") (pinfunction "2_2") (pintype "passive"))
      (node (ref "C227") (pin "2") (pinfunction "2_2") (pintype "passive"))
      (node (ref "C240") (pin "1") (pinfunction "1_1") (pintype "passive"))
      (node (ref "C253") (pin "1") (pinfunction "1_1") (pintype "passive"))
      (node (ref "C254") (pin "2") (pinfunction "2_2") (pintype "passive"))
      (node (ref "C264") (pin "1") (pinfunction "1_1") (pintype "passive"))
      (node (ref "C318") (pin "2") (pinfunction "2_2") (pintype "passive"))
      (node (ref "C319") (pin "1") (pinfunction "1_1") (pintype "passive"))
      (node (ref "C326") (pin "1") (pinfunction "1_1") (pintype "passive"))
      (node (ref "C327") (pin "2") (pinfunction "2_2") (pintype "passive"))
      (node (ref "C328") (pin "1") (pinfunction "1_1") (pintype "passive"))
      (node (ref "C329") (pin "2") (pinfunction "2_2") (pintype "passive"))
      (node (ref "C331") (pin "1") (pinfunction "1_1") (pintype "passive"))
      (node (ref "C332") (pin "2") (pinfunction "2_2") (pintype "passive"))
      (node (ref "C335") (pin "2") (pinfunction "2_2") (pintype "passive"))
      (node (ref "C336") (pin "1") (pinfunction "1_1") (pintype "passive"))
      (node (ref "C337") (pin "2") (pinfunction "2_2") (pintype "passive"))
      (node (ref "C338") (pin "1") (pinfunction "1_1") (pintype "passive"))
      (node (ref "C436") (pin "1") (pinfunction "1_1") (pintype "passive"))
      (node (ref "C437") (pin "2") (pinfunction "2_2") (pintype "passive"))
      (node (ref "C447") (pin "1") (pinfunction "1_1") (pintype "passive"))
      (node (ref "C457") (pin "2") (pinfunction "2_2") (pintype "passive"))
      (node (ref "C464") (pin "1") (pinfunction "1_1") (pintype "passive"))
      (node (ref "C465") (pin "2") (pinfunction "2_2") (pintype "passive"))
      (node (ref "IC21") (pin "11") (pinfunction "LE_11") (pintype "input"))
      (node (ref "IC21") (pin "18") (pinfunction "VCC_18") (pintype "power_in"))
      (node (ref "IC21") (pin "25") (pinfunction "VCC_25") (pintype "power_in"))
      (node (ref "IC21") (pin "31") (pinfunction "VCC_31") (pintype "power_in"))
      (node (ref "IC21") (pin "35") (pinfunction "VCC_35") (pintype "power_in"))
      (node (ref "IC21") (pin "38") (pinfunction "VCC_38") (pintype "power_in"))
      (node (ref "IC21") (pin "42") (pinfunction "VCC_42") (pintype "power_in"))
      (node (ref "IC21") (pin "44") (pinfunction "BIASVCC_44") (pintype "input"))
      (node (ref "IC21") (pin "47") (pinfunction "VCC_47") (pintype "input"))
      (node (ref "IC21") (pin "7") (pinfunction "VCC_7") (pintype "power_in"))
      (node (ref "IC22") (pin "11") (pinfunction "LE_11") (pintype "input"))
      (node (ref "IC22") (pin "18") (pinfunction "VCC_18") (pintype "power_in"))
      (node (ref "IC22") (pin "25") (pinfunction "VCC_25") (pintype "power_in"))
      (node (ref "IC22") (pin "31") (pinfunction "VCC_31") (pintype "power_in"))
      (node (ref "IC22") (pin "35") (pinfunction "VCC_35") (pintype "power_in"))
      (node (ref "IC22") (pin "38") (pinfunction "VCC_38") (pintype "power_in"))
      (node (ref "IC22") (pin "42") (pinfunction "VCC_42") (pintype "power_in"))
      (node (ref "IC22") (pin "44") (pinfunction "BIASVCC_44") (pintype "input"))
      (node (ref "IC22") (pin "47") (pinfunction "VCC_47") (pintype "input"))
      (node (ref "IC22") (pin "7") (pinfunction "VCC_7") (pintype "power_in"))
      (node (ref "IC26") (pin "1") (pinfunction "~{1OEBY}_1") (pintype "input"))
      (node (ref "IC26") (pin "11") (pinfunction "LE_11") (pintype "input"))
      (node (ref "IC26") (pin "18") (pinfunction "VCC_18") (pintype "power_in"))
      (node (ref "IC26") (pin "25") (pinfunction "VCC_25") (pintype "power_in"))
      (node (ref "IC26") (pin "31") (pinfunction "VCC_31") (pintype "power_in"))
      (node (ref "IC26") (pin "35") (pinfunction "VCC_35") (pintype "power_in"))
      (node (ref "IC26") (pin "38") (pinfunction "VCC_38") (pintype "power_in"))
      (node (ref "IC26") (pin "42") (pinfunction "VCC_42") (pintype "power_in"))
      (node (ref "IC26") (pin "44") (pinfunction "BIASVCC_44") (pintype "input"))
      (node (ref "IC26") (pin "47") (pinfunction "VCC_47") (pintype "input"))
      (node (ref "IC26") (pin "7") (pinfunction "VCC_7") (pintype "power_in"))
      (node (ref "IC33") (pin "11") (pinfunction "LE_11") (pintype "input"))
      (node (ref "IC33") (pin "18") (pinfunction "VCC_18") (pintype "power_in"))
      (node (ref "IC33") (pin "25") (pinfunction "VCC_25") (pintype "power_in"))
      (node (ref "IC33") (pin "31") (pinfunction "VCC_31") (pintype "power_in"))
      (node (ref "IC33") (pin "35") (pinfunction "VCC_35") (pintype "power_in"))
      (node (ref "IC33") (pin "38") (pinfunction "VCC_38") (pintype "power_in"))
      (node (ref "IC33") (pin "41") (pinfunction "2OEAB_41") (pintype "input"))
      (node (ref "IC33") (pin "42") (pinfunction "VCC_42") (pintype "power_in"))
      (node (ref "IC33") (pin "44") (pinfunction "BIASVCC_44") (pintype "input"))
      (node (ref "IC33") (pin "47") (pinfunction "VCC_47") (pintype "input"))
      (node (ref "IC33") (pin "7") (pinfunction "VCC_7") (pintype "power_in"))
      (node (ref "IC33") (pin "8") (pinfunction "2~{OEBY}_8") (pintype "input"))
      (node (ref "R158") (pin "1") (pinfunction "1_1") (pintype "passive"))
      (node (ref "R203") (pin "2") (pinfunction "2_2") (pintype "passive"))
      (node (ref "R316") (pin "2") (pinfunction "2_2") (pintype "passive"))
    )
    (net (code "88") (name "unconnected-(IC26-1Y-Pad3)") (class "Default")
      (node (ref "IC26") (pin "3") (pinfunction "1Y_3") (pintype "output+no_connect"))
    )
    (net (code "89") (name "unconnected-(IC33-2Y-Pad6)") (class "Default")
      (node (ref "IC33") (pin "6") (pinfunction "2Y_6") (pintype "output+no_connect"))
    )
  )
)
